# Power_Distro_PCB.net
KiCad netlist of a schematic drawn in EAGLE
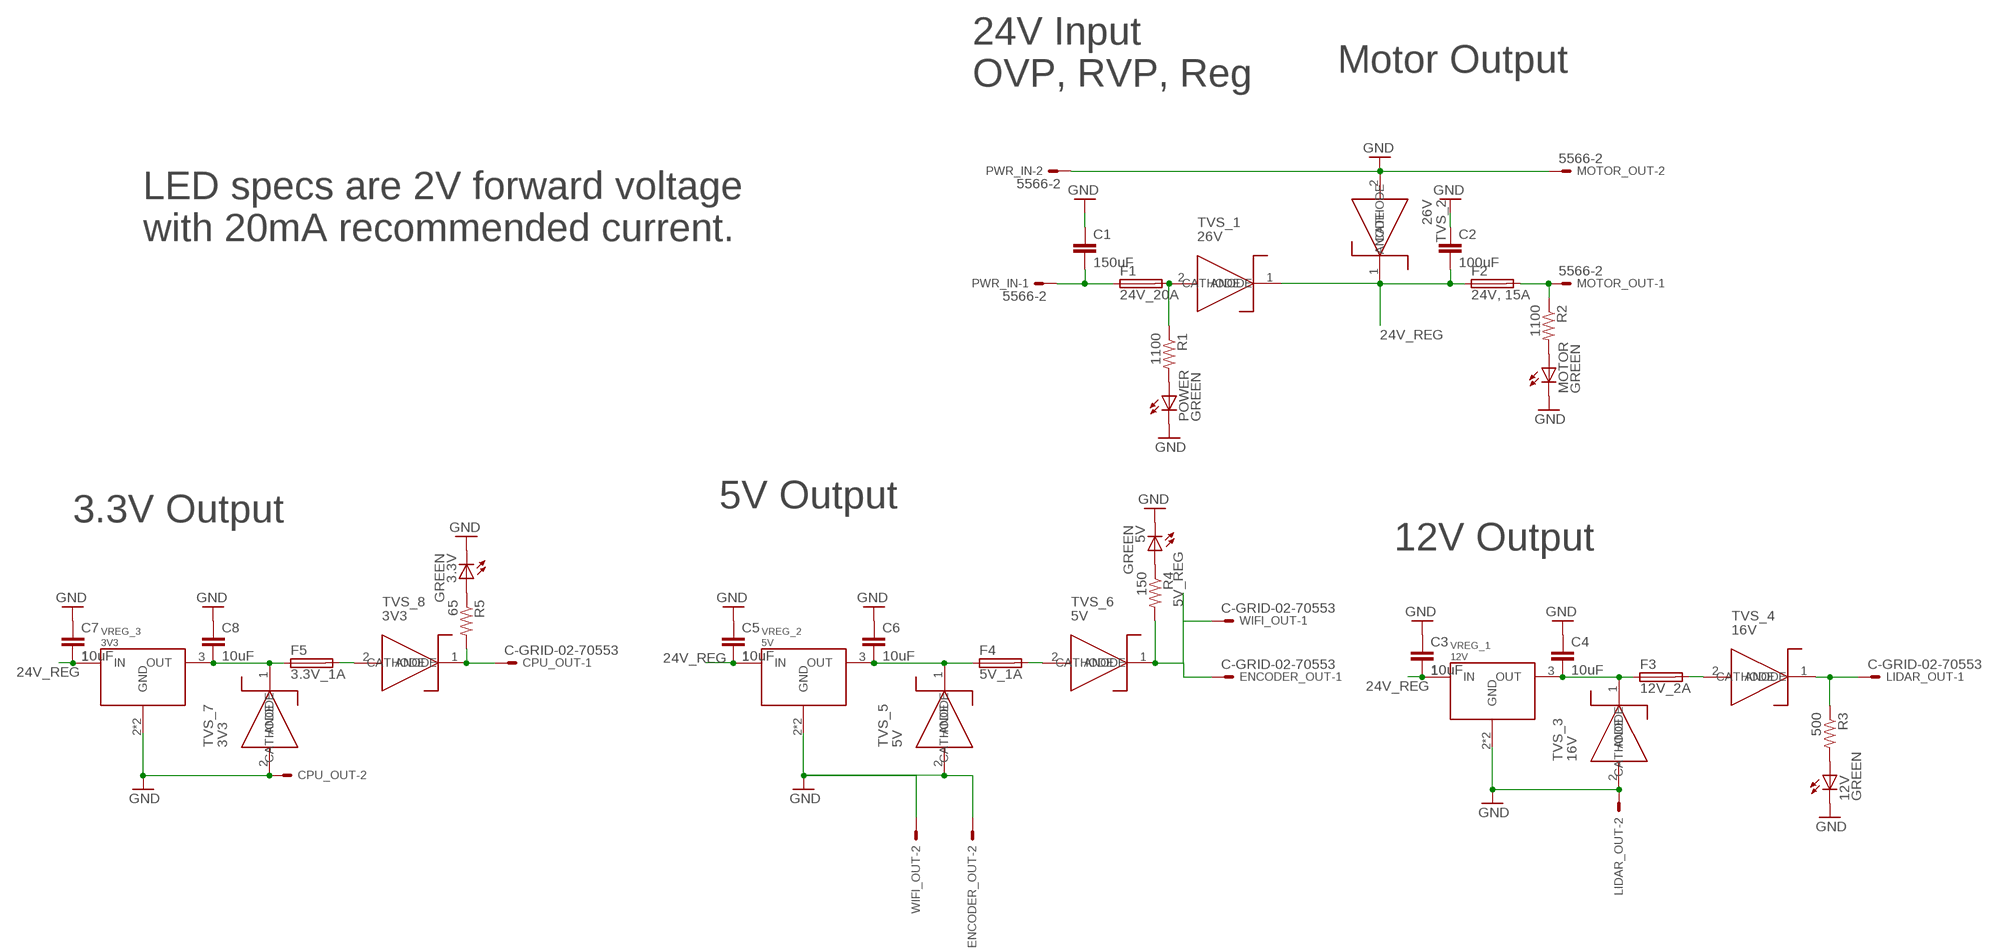
[diagram p0: schematic, sheet 1]

(export (version "E")
  (design (tool "Eeschema 10.0.6"))
  (components
    (comp (ref "3.3V")
      (value "GREEN")
      (footprint "eagle-import:SML1206")
      (libsource (lib "eagle-import") (part "LEDSML1206"))
    )
    (comp (ref "5V")
      (value "GREEN")
      (footprint "eagle-import:SML1206")
      (libsource (lib "eagle-import") (part "LEDSML1206"))
    )
    (comp (ref "12V")
      (value "GREEN")
      (footprint "eagle-import:SML1206")
      (libsource (lib "eagle-import") (part "LEDSML1206"))
    )
    (comp (ref "C1")
      (value "150uF")
      (footprint "eagle-import:C1206")
      (libsource (lib "eagle-import") (part "C-EUC1206"))
    )
    (comp (ref "C2")
      (value "100uF")
      (footprint "eagle-import:C1206")
      (libsource (lib "eagle-import") (part "C-EUC1206"))
    )
    (comp (ref "C3")
      (value "10uF")
      (footprint "eagle-import:C1206")
      (libsource (lib "eagle-import") (part "C-EUC1206"))
    )
    (comp (ref "C4")
      (value "10uF")
      (footprint "eagle-import:C1206")
      (libsource (lib "eagle-import") (part "C-EUC1206"))
    )
    (comp (ref "C5")
      (value "10uF")
      (footprint "eagle-import:C1206")
      (libsource (lib "eagle-import") (part "C-EUC1206"))
    )
    (comp (ref "C6")
      (value "10uF")
      (footprint "eagle-import:C1206")
      (libsource (lib "eagle-import") (part "C-EUC1206"))
    )
    (comp (ref "C7")
      (value "10uF")
      (footprint "eagle-import:C1206")
      (libsource (lib "eagle-import") (part "C-EUC1206"))
    )
    (comp (ref "C8")
      (value "10uF")
      (footprint "eagle-import:C1206")
      (libsource (lib "eagle-import") (part "C-EUC1206"))
    )
    (comp (ref "CPU_OUT")
      (value "C-GRID-02-70553")
      (footprint "eagle-import:70553-02")
      (libsource (lib "eagle-import") (part "C-GRID-02-70553"))
    )
    (comp (ref "ENCODER_OUT")
      (value "C-GRID-02-70553")
      (footprint "eagle-import:70553-02")
      (libsource (lib "eagle-import") (part "C-GRID-02-70553"))
    )
    (comp (ref "F1")
      (value "24V_20A")
      (footprint "eagle-import:TE5")
      (libsource (lib "eagle-import") (part "TE5"))
    )
    (comp (ref "F2")
      (value "24V, 15A")
      (footprint "eagle-import:TE5")
      (libsource (lib "eagle-import") (part "TE5"))
    )
    (comp (ref "F3")
      (value "12V_2A")
      (footprint "eagle-import:TE5")
      (libsource (lib "eagle-import") (part "TE5"))
    )
    (comp (ref "F4")
      (value "5V_1A")
      (footprint "eagle-import:TE5")
      (libsource (lib "eagle-import") (part "TE5"))
    )
    (comp (ref "F5")
      (value "3.3V_1A")
      (footprint "eagle-import:TE5")
      (libsource (lib "eagle-import") (part "TE5"))
    )
    (comp (ref "LIDAR_OUT")
      (value "C-GRID-02-70553")
      (footprint "eagle-import:70553-02")
      (libsource (lib "eagle-import") (part "C-GRID-02-70553"))
    )
    (comp (ref "MOTOR")
      (value "GREEN")
      (footprint "eagle-import:SML1206")
      (libsource (lib "eagle-import") (part "LEDSML1206"))
    )
    (comp (ref "MOTOR_OUT")
      (value "5566-2")
      (footprint "eagle-import:5566-2")
      (libsource (lib "eagle-import") (part "5566-2"))
    )
    (comp (ref "POWER")
      (value "GREEN")
      (footprint "eagle-import:SML1206")
      (libsource (lib "eagle-import") (part "LEDSML1206"))
    )
    (comp (ref "PWR_IN")
      (value "5566-2")
      (footprint "eagle-import:5566-2")
      (libsource (lib "eagle-import") (part "5566-2"))
    )
    (comp (ref "R1")
      (value "1100")
      (footprint "eagle-import:R1206")
      (libsource (lib "eagle-import") (part "R-US_R1206"))
    )
    (comp (ref "R2")
      (value "1100")
      (footprint "eagle-import:R1206")
      (libsource (lib "eagle-import") (part "R-US_R1206"))
    )
    (comp (ref "R3")
      (value "500")
      (footprint "eagle-import:R1206")
      (libsource (lib "eagle-import") (part "R-US_R1206"))
    )
    (comp (ref "R4")
      (value "150")
      (footprint "eagle-import:R1206")
      (libsource (lib "eagle-import") (part "R-US_R1206"))
    )
    (comp (ref "R5")
      (value "65")
      (footprint "eagle-import:R1206")
      (libsource (lib "eagle-import") (part "R-US_R1206"))
    )
    (comp (ref "TVS_1")
      (value "26V")
      (footprint "eagle-import:DO-214AC")
      (libsource (lib "eagle-import") (part "SMAJ26A_TVSSMA"))
    )
    (comp (ref "TVS_2")
      (value "26V")
      (footprint "eagle-import:DO-214AC")
      (libsource (lib "eagle-import") (part "SMAJ26A_TVSSMA"))
    )
    (comp (ref "TVS_3")
      (value "16V")
      (footprint "eagle-import:DO-214AC")
      (libsource (lib "eagle-import") (part "PRSMA16_TVS"))
    )
    (comp (ref "TVS_4")
      (value "16V")
      (footprint "eagle-import:DO-214AC")
      (libsource (lib "eagle-import") (part "PRSMA16_TVS"))
    )
    (comp (ref "TVS_5")
      (value "5V")
      (footprint "eagle-import:DO-214AC")
      (libsource (lib "eagle-import") (part "SMAJ5.0_TVSSMA"))
    )
    (comp (ref "TVS_6")
      (value "5V")
      (footprint "eagle-import:DO-214AC")
      (libsource (lib "eagle-import") (part "SMAJ5.0_TVSSMA"))
    )
    (comp (ref "TVS_7")
      (value "3V3")
      (footprint "eagle-import:DO-214AA")
      (libsource (lib "eagle-import") (part "SMBJ3V3_TVSSMB"))
    )
    (comp (ref "TVS_8")
      (value "3V3")
      (footprint "eagle-import:DO-214AA")
      (libsource (lib "eagle-import") (part "SMBJ3V3_TVSSMB"))
    )
    (comp (ref "VREG_1")
      (value "12V")
      (footprint "eagle-import:TO-263-3")
      (libsource (lib "eagle-import") (part "HIGH-CURRENT_REGSMA"))
    )
    (comp (ref "VREG_2")
      (value "5V")
      (footprint "eagle-import:TO-263-3")
      (libsource (lib "eagle-import") (part "HIGH-CURRENT_REGSMA"))
    )
    (comp (ref "VREG_3")
      (value "3V3")
      (footprint "eagle-import:TO-263-3")
      (libsource (lib "eagle-import") (part "HIGH-CURRENT_REGSMA"))
    )
    (comp (ref "WIFI_OUT")
      (value "C-GRID-02-70553")
      (footprint "eagle-import:70553-02")
      (libsource (lib "eagle-import") (part "C-GRID-02-70553"))
    )
  )
  (nets
    (net (code "1") (name "/5V_REG") (class "Default")
      (node (ref "ENCODER_OUT") (pin "1") (pinfunction "S_1") (pintype "passive"))
      (node (ref "R4") (pin "2") (pinfunction "2_2") (pintype "passive"))
      (node (ref "TVS_6") (pin "1") (pinfunction "CATHODE_1") (pintype "bidirectional"))
      (node (ref "WIFI_OUT") (pin "1") (pinfunction "S_1") (pintype "passive"))
    )
    (net (code "2") (name "/24V_REG") (class "Default")
      (node (ref "C2") (pin "2") (pinfunction "2_2") (pintype "passive"))
      (node (ref "C3") (pin "2") (pinfunction "2_2") (pintype "passive"))
      (node (ref "C5") (pin "2") (pinfunction "2_2") (pintype "passive"))
      (node (ref "C7") (pin "2") (pinfunction "2_2") (pintype "passive"))
      (node (ref "F2") (pin "1") (pinfunction "1_1") (pintype "passive"))
      (node (ref "TVS_1") (pin "1") (pinfunction "CATHODE_1") (pintype "bidirectional"))
      (node (ref "TVS_2") (pin "1") (pinfunction "CATHODE_1") (pintype "bidirectional"))
      (node (ref "VREG_1") (pin "1") (pinfunction "IN_1") (pintype "bidirectional"))
      (node (ref "VREG_2") (pin "1") (pinfunction "IN_1") (pintype "bidirectional"))
      (node (ref "VREG_3") (pin "1") (pinfunction "IN_1") (pintype "bidirectional"))
    )
    (net (code "3") (name "GND") (class "Default")
      (node (ref "12V") (pin "C") (pinfunction "C_C") (pintype "passive"))
      (node (ref "3.3V") (pin "C") (pinfunction "C_C") (pintype "passive"))
      (node (ref "5V") (pin "C") (pinfunction "C_C") (pintype "passive"))
      (node (ref "C1") (pin "1") (pinfunction "1_1") (pintype "passive"))
      (node (ref "C2") (pin "1") (pinfunction "1_1") (pintype "passive"))
      (node (ref "C3") (pin "1") (pinfunction "1_1") (pintype "passive"))
      (node (ref "C4") (pin "1") (pinfunction "1_1") (pintype "passive"))
      (node (ref "C5") (pin "1") (pinfunction "1_1") (pintype "passive"))
      (node (ref "C6") (pin "1") (pinfunction "1_1") (pintype "passive"))
      (node (ref "C7") (pin "1") (pinfunction "1_1") (pintype "passive"))
      (node (ref "C8") (pin "1") (pinfunction "1_1") (pintype "passive"))
      (node (ref "CPU_OUT") (pin "2") (pinfunction "S_2") (pintype "passive"))
      (node (ref "ENCODER_OUT") (pin "2") (pinfunction "S_2") (pintype "passive"))
      (node (ref "LIDAR_OUT") (pin "2") (pinfunction "S_2") (pintype "passive"))
      (node (ref "MOTOR") (pin "C") (pinfunction "C_C") (pintype "passive"))
      (node (ref "MOTOR_OUT") (pin "2") (pinfunction "S_2") (pintype "passive"))
      (node (ref "POWER") (pin "C") (pinfunction "C_C") (pintype "passive"))
      (node (ref "PWR_IN") (pin "2") (pinfunction "S_2") (pintype "passive"))
      (node (ref "TVS_2") (pin "2") (pinfunction "ANODE_2") (pintype "bidirectional"))
      (node (ref "TVS_3") (pin "2") (pinfunction "ANODE_2") (pintype "bidirectional"))
      (node (ref "TVS_5") (pin "2") (pinfunction "ANODE_2") (pintype "bidirectional"))
      (node (ref "TVS_7") (pin "2") (pinfunction "ANODE_2") (pintype "bidirectional"))
      (node (ref "VREG_1") (pin "2") (pinfunction "GND_2") (pintype "bidirectional"))
      (node (ref "VREG_1") (pin "4") (pinfunction "GND_4") (pintype "bidirectional"))
      (node (ref "VREG_2") (pin "2") (pinfunction "GND_2") (pintype "bidirectional"))
      (node (ref "VREG_2") (pin "4") (pinfunction "GND_4") (pintype "bidirectional"))
      (node (ref "VREG_3") (pin "2") (pinfunction "GND_2") (pintype "bidirectional"))
      (node (ref "VREG_3") (pin "4") (pinfunction "GND_4") (pintype "bidirectional"))
      (node (ref "WIFI_OUT") (pin "2") (pinfunction "S_2") (pintype "passive"))
    )
    (net (code "4") (name "Net-(3.3V-PadA)") (class "Default")
      (node (ref "3.3V") (pin "A") (pinfunction "A_A") (pintype "passive"))
      (node (ref "R5") (pin "1") (pinfunction "1_1") (pintype "passive"))
    )
    (net (code "5") (name "Net-(5V-PadA)") (class "Default")
      (node (ref "5V") (pin "A") (pinfunction "A_A") (pintype "passive"))
      (node (ref "R4") (pin "1") (pinfunction "1_1") (pintype "passive"))
    )
    (net (code "6") (name "Net-(12V-PadA)") (class "Default")
      (node (ref "12V") (pin "A") (pinfunction "A_A") (pintype "passive"))
      (node (ref "R3") (pin "2") (pinfunction "2_2") (pintype "passive"))
    )
    (net (code "7") (name "Net-(CPU_OUTA-S)") (class "Default")
      (node (ref "CPU_OUT") (pin "1") (pinfunction "S_1") (pintype "passive"))
      (node (ref "R5") (pin "2") (pinfunction "2_2") (pintype "passive"))
      (node (ref "TVS_8") (pin "1") (pinfunction "CATHODE_1") (pintype "bidirectional"))
    )
    (net (code "8") (name "Net-(LIDAR_OUTA-S)") (class "Default")
      (node (ref "LIDAR_OUT") (pin "1") (pinfunction "S_1") (pintype "passive"))
      (node (ref "R3") (pin "1") (pinfunction "1_1") (pintype "passive"))
      (node (ref "TVS_4") (pin "1") (pinfunction "CATHODE_1") (pintype "bidirectional"))
    )
    (net (code "9") (name "Net-(MOTOR-PadA)") (class "Default")
      (node (ref "MOTOR") (pin "A") (pinfunction "A_A") (pintype "passive"))
      (node (ref "R2") (pin "2") (pinfunction "2_2") (pintype "passive"))
    )
    (net (code "10") (name "Net-(MOTOR_OUTA-S)") (class "Default")
      (node (ref "F2") (pin "2") (pinfunction "2_2") (pintype "passive"))
      (node (ref "MOTOR_OUT") (pin "1") (pinfunction "S_1") (pintype "passive"))
      (node (ref "R2") (pin "1") (pinfunction "1_1") (pintype "passive"))
    )
    (net (code "11") (name "Net-(POWER-PadA)") (class "Default")
      (node (ref "POWER") (pin "A") (pinfunction "A_A") (pintype "passive"))
      (node (ref "R1") (pin "2") (pinfunction "2_2") (pintype "passive"))
    )
    (net (code "12") (name "Net-(PWR_INA-S)") (class "Default")
      (node (ref "C1") (pin "2") (pinfunction "2_2") (pintype "passive"))
      (node (ref "F1") (pin "1") (pinfunction "1_1") (pintype "passive"))
      (node (ref "PWR_IN") (pin "1") (pinfunction "S_1") (pintype "passive"))
    )
    (net (code "13") (name "Net-(TVS_1-ANODE)") (class "Default")
      (node (ref "F1") (pin "2") (pinfunction "2_2") (pintype "passive"))
      (node (ref "R1") (pin "1") (pinfunction "1_1") (pintype "passive"))
      (node (ref "TVS_1") (pin "2") (pinfunction "ANODE_2") (pintype "bidirectional"))
    )
    (net (code "14") (name "Net-(TVS_3-CATHODE)") (class "Default")
      (node (ref "C4") (pin "2") (pinfunction "2_2") (pintype "passive"))
      (node (ref "F3") (pin "1") (pinfunction "1_1") (pintype "passive"))
      (node (ref "TVS_3") (pin "1") (pinfunction "CATHODE_1") (pintype "bidirectional"))
      (node (ref "VREG_1") (pin "3") (pinfunction "OUT_3") (pintype "bidirectional"))
    )
    (net (code "15") (name "Net-(TVS_4-ANODE)") (class "Default")
      (node (ref "F3") (pin "2") (pinfunction "2_2") (pintype "passive"))
      (node (ref "TVS_4") (pin "2") (pinfunction "ANODE_2") (pintype "bidirectional"))
    )
    (net (code "16") (name "Net-(TVS_5-CATHODE)") (class "Default")
      (node (ref "C6") (pin "2") (pinfunction "2_2") (pintype "passive"))
      (node (ref "F4") (pin "1") (pinfunction "1_1") (pintype "passive"))
      (node (ref "TVS_5") (pin "1") (pinfunction "CATHODE_1") (pintype "bidirectional"))
      (node (ref "VREG_2") (pin "3") (pinfunction "OUT_3") (pintype "bidirectional"))
    )
    (net (code "17") (name "Net-(TVS_6-ANODE)") (class "Default")
      (node (ref "F4") (pin "2") (pinfunction "2_2") (pintype "passive"))
      (node (ref "TVS_6") (pin "2") (pinfunction "ANODE_2") (pintype "bidirectional"))
    )
    (net (code "18") (name "Net-(TVS_7-CATHODE)") (class "Default")
      (node (ref "C8") (pin "2") (pinfunction "2_2") (pintype "passive"))
      (node (ref "F5") (pin "1") (pinfunction "1_1") (pintype "passive"))
      (node (ref "TVS_7") (pin "1") (pinfunction "CATHODE_1") (pintype "bidirectional"))
      (node (ref "VREG_3") (pin "3") (pinfunction "OUT_3") (pintype "bidirectional"))
    )
    (net (code "19") (name "Net-(TVS_8-ANODE)") (class "Default")
      (node (ref "F5") (pin "2") (pinfunction "2_2") (pintype "passive"))
      (node (ref "TVS_8") (pin "2") (pinfunction "ANODE_2") (pintype "bidirectional"))
    )
  )
)
